# MCU.net
KiCad netlist of a schematic drawn in Altium Designer
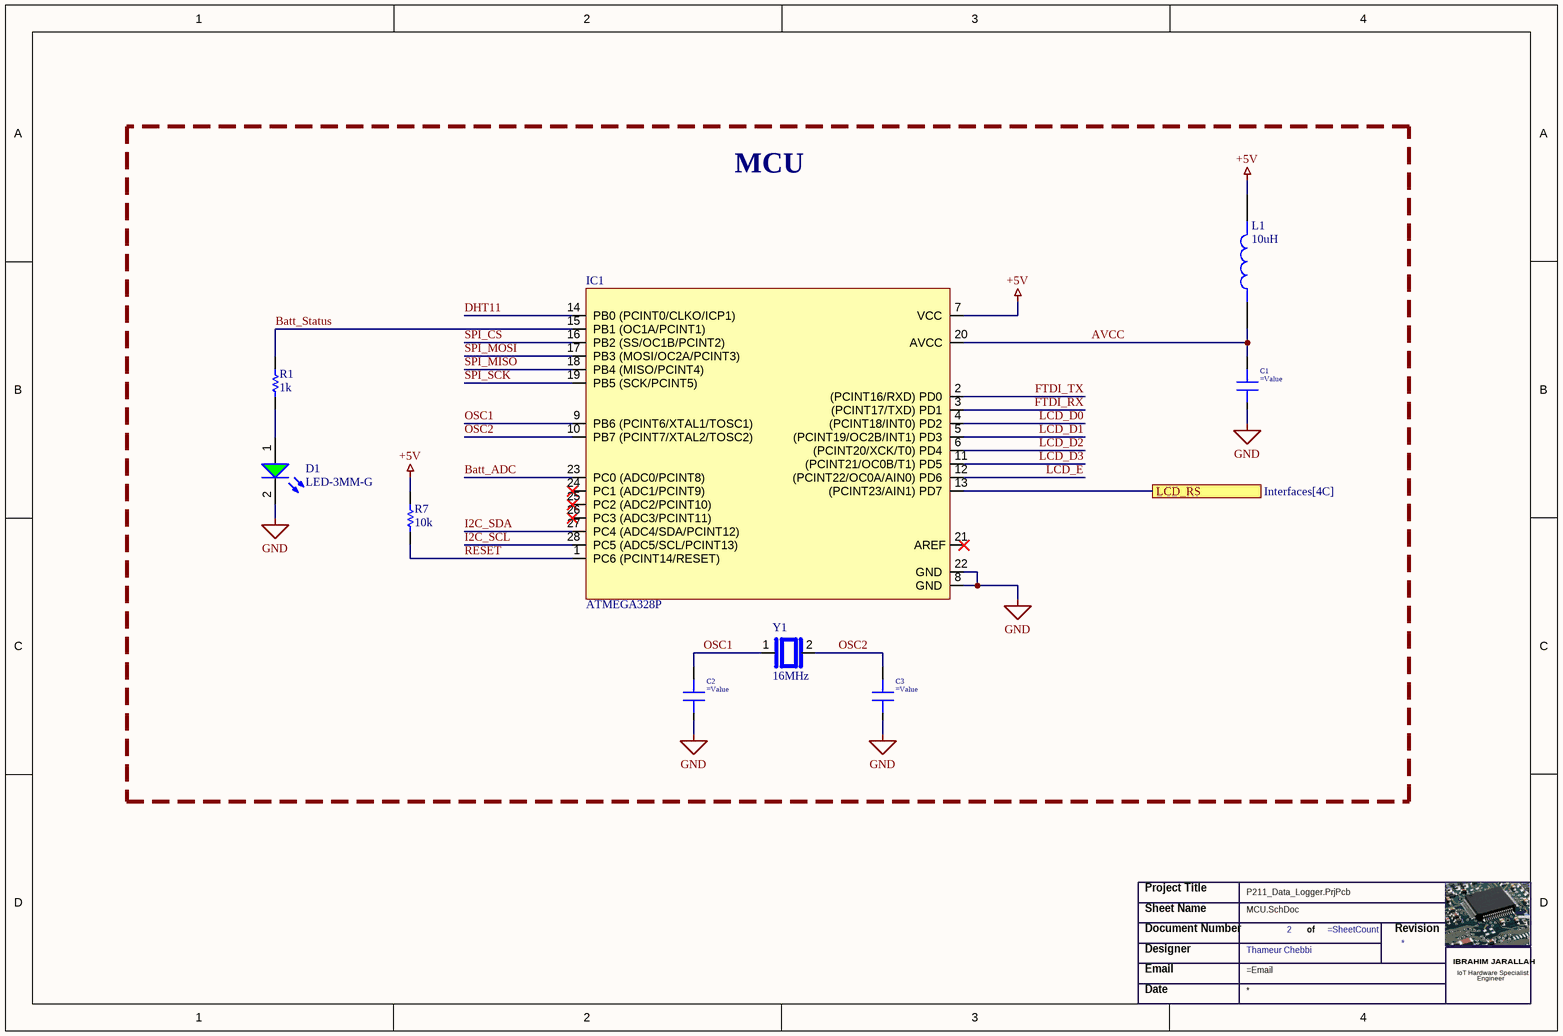
[diagram p0: MCU.SchDoc]

(export (version "E")
  (design (tool "Eeschema 10.0.6"))
  (components
    (comp (ref "C1")
      (value "~")
      (footprint "C 0805(2012)x0.85")
      (description "SMD 0805     50V X7R 10%")
      (fields (field (name "MANUFACTURER") "Samsung") (field (name "PUBLISHER") "Hefest"))
      (libsource (lib "SCH_THA") (part "C 0805    50V X7R - 0*"))
    )
    (comp (ref "C2")
      (value "~")
      (footprint "C 0805(2012)x0.85")
      (description "SMD 0805     50V X7R 10%")
      (fields (field (name "MANUFACTURER") "Samsung") (field (name "PUBLISHER") "Hefest"))
      (libsource (lib "SCH_THA") (part "C 0805    50V X7R - 0*"))
    )
    (comp (ref "C3")
      (value "~")
      (footprint "C 0805(2012)x0.85")
      (description "SMD 0805     50V X7R 10%")
      (fields (field (name "MANUFACTURER") "Samsung") (field (name "PUBLISHER") "Hefest"))
      (libsource (lib "SCH_THA") (part "C 0805    50V X7R - 0*"))
    )
    (comp (ref "D1")
      (value "LED-3MM-G")
      (footprint "LED-2.54MM-G")
      (libsource (lib "SCH_THA") (part "LED-3MM-G"))
    )
    (comp (ref "IC1")
      (value "ATMEGA328P")
      (footprint "DIP28_P2.54mm_7.62mm")
      (description "Microcontroller, ATmega328P, 8-bit, PDIP-28 32kB Flash")
      (libsource (lib "Symbol_Lib") (part "IC_ATMEGA328P_PDIP"))
    )
    (comp (ref "L1")
      (value "10uH")
      (footprint "IND_LQH31MN100J03L")
      (description "Wire Wound Ferrite Inductor for General Circuits")
      (fields (field (name "MF") "{'manufacturer': u'Murata'}") (field (name "MP") "LQH31MN100J03L"))
      (libsource (lib "SCH_THA") (part "LQH31MN100J03L"))
    )
    (comp (ref "R1")
      (value "1k")
      (footprint "RESC2013X50X30LL20T20")
      (libsource (lib "SCH_THA") (part "RES-0805-SMD"))
    )
    (comp (ref "R7")
      (value "10k")
      (footprint "RESC2013X50X30LL20T20")
      (libsource (lib "SCH_THA") (part "RES-0805-SMD"))
    )
    (comp (ref "Y1")
      (value "16MHz")
      (footprint "XTAL_HC49P488W43L1150T466H350")
      (description "HC49US Series 16 MHz Â±30 ppm 18 pF -20 to +70 Â°C Through Hole AT-CUT Crystal")
      (fields
        (field (name "MF") "{'manufacturer': u'Citizen Finedevice'}")
        (field (name "MP") "HC-49/U-S16000000ABJB")
      )
      (libsource (lib "SCH_THA") (part "HC-49/U-S16000000ABJB"))
    )
  )
  (nets
    (net (code "1") (name "+5V") (class "Default")
      (node (ref "IC1") (pin "7") (pinfunction "VCC_7") (pintype "power_in"))
      (node (ref "L1") (pin "2") (pinfunction "2_2") (pintype "passive"))
      (node (ref "R7") (pin "1") (pinfunction "1_1") (pintype "passive"))
    )
    (net (code "2") (name "/AVCC") (class "Default")
      (node (ref "C1") (pin "2") (pinfunction "2_2") (pintype "passive"))
      (node (ref "IC1") (pin "20") (pinfunction "AVCC_20") (pintype "power_in"))
      (node (ref "L1") (pin "1") (pinfunction "1_1") (pintype "passive"))
    )
    (net (code "3") (name "/Batt_ADC") (class "Default")
      (node (ref "IC1") (pin "23") (pinfunction "PC0_(ADC0/PCINT8)_23") (pintype "passive"))
    )
    (net (code "4") (name "/Batt_Status") (class "Default")
      (node (ref "IC1") (pin "15") (pinfunction "PB1_(OC1A/PCINT1)_15") (pintype "passive"))
      (node (ref "R1") (pin "1") (pinfunction "1_1") (pintype "passive"))
    )
    (net (code "5") (name "/DHT11") (class "Default")
      (node (ref "IC1") (pin "14") (pinfunction "PB0_(PCINT0/CLKO/ICP1)_14") (pintype "passive"))
    )
    (net (code "6") (name "/FTDI_RX") (class "Default")
      (node (ref "IC1") (pin "3") (pinfunction "(PCINT17/TXD)_PD1_3") (pintype "passive"))
    )
    (net (code "7") (name "/FTDI_TX") (class "Default")
      (node (ref "IC1") (pin "2") (pinfunction "(PCINT16/RXD)_PD0_2") (pintype "passive"))
    )
    (net (code "8") (name "/I2C_SCL") (class "Default")
      (node (ref "IC1") (pin "28") (pinfunction "PC5_(ADC5/SCL/PCINT13)_28") (pintype "passive"))
    )
    (net (code "9") (name "/I2C_SDA") (class "Default")
      (node (ref "IC1") (pin "27") (pinfunction "PC4_(ADC4/SDA/PCINT12)_27") (pintype "passive"))
    )
    (net (code "10") (name "/LCD_D0") (class "Default")
      (node (ref "IC1") (pin "4") (pinfunction "(PCINT18/INT0)_PD2_4") (pintype "passive"))
    )
    (net (code "11") (name "/LCD_D1") (class "Default")
      (node (ref "IC1") (pin "5") (pinfunction "(PCINT19/OC2B/INT1)_PD3_5") (pintype "passive"))
    )
    (net (code "12") (name "/LCD_D2") (class "Default")
      (node (ref "IC1") (pin "6") (pinfunction "(PCINT20/XCK/T0)_PD4_6") (pintype "passive"))
    )
    (net (code "13") (name "/LCD_D3") (class "Default")
      (node (ref "IC1") (pin "11") (pinfunction "(PCINT21/OC0B/T1)_PD5_11") (pintype "passive"))
    )
    (net (code "14") (name "/LCD_E") (class "Default")
      (node (ref "IC1") (pin "12") (pinfunction "(PCINT22/OC0A/AIN0)_PD6_12") (pintype "passive"))
    )
    (net (code "15") (name "/LCD_RS") (class "Default")
      (node (ref "IC1") (pin "13") (pinfunction "(PCINT23/AIN1)_PD7_13") (pintype "passive"))
    )
    (net (code "16") (name "/OSC1") (class "Default")
      (node (ref "C2") (pin "2") (pinfunction "2_2") (pintype "passive"))
      (node (ref "IC1") (pin "9") (pinfunction "PB6_(PCINT6/XTAL1/TOSC1)_9") (pintype "passive"))
      (node (ref "Y1") (pin "1") (pinfunction "1_1") (pintype "passive"))
    )
    (net (code "17") (name "/OSC2") (class "Default")
      (node (ref "C3") (pin "2") (pinfunction "2_2") (pintype "passive"))
      (node (ref "IC1") (pin "10") (pinfunction "PB7_(PCINT7/XTAL2/TOSC2)_10") (pintype "passive"))
      (node (ref "Y1") (pin "2") (pinfunction "2_2") (pintype "passive"))
    )
    (net (code "18") (name "/RESET") (class "Default")
      (node (ref "IC1") (pin "1") (pinfunction "PC6_(PCINT14/RESET)_1") (pintype "passive"))
      (node (ref "R7") (pin "2") (pinfunction "2_2") (pintype "passive"))
    )
    (net (code "19") (name "/SPI_CS") (class "Default")
      (node (ref "IC1") (pin "16") (pinfunction "PB2_(SS/OC1B/PCINT2)_16") (pintype "passive"))
    )
    (net (code "20") (name "/SPI_MISO") (class "Default")
      (node (ref "IC1") (pin "18") (pinfunction "PB4_(MISO/PCINT4)_18") (pintype "passive"))
    )
    (net (code "21") (name "/SPI_MOSI") (class "Default")
      (node (ref "IC1") (pin "17") (pinfunction "PB3_(MOSI/OC2A/PCINT3)_17") (pintype "passive"))
    )
    (net (code "22") (name "/SPI_SCK") (class "Default")
      (node (ref "IC1") (pin "19") (pinfunction "PB5_(SCK/PCINT5)_19") (pintype "passive"))
    )
    (net (code "23") (name "GND") (class "Default")
      (node (ref "C1") (pin "1") (pinfunction "1_1") (pintype "passive"))
      (node (ref "C2") (pin "1") (pinfunction "1_1") (pintype "passive"))
      (node (ref "C3") (pin "1") (pinfunction "1_1") (pintype "passive"))
      (node (ref "D1") (pin "2") (pinfunction "K_2") (pintype "passive"))
      (node (ref "IC1") (pin "22") (pinfunction "GND_22") (pintype "power_in"))
      (node (ref "IC1") (pin "8") (pinfunction "GND_8") (pintype "power_in"))
    )
    (net (code "24") (name "Net-(D1-A)") (class "Default")
      (node (ref "D1") (pin "1") (pinfunction "A_1") (pintype "passive"))
      (node (ref "R1") (pin "2") (pinfunction "2_2") (pintype "passive"))
    )
    (net (code "25") (name "unconnected-(IC1-AREF-Pad21)") (class "Default")
      (node (ref "IC1") (pin "21") (pinfunction "AREF_21") (pintype "power_in+no_connect"))
    )
    (net (code "26") (name "unconnected-(IC1-PC1_(ADC1{slash}PCINT9)-Pad24)") (class "Default")
      (node (ref "IC1") (pin "24") (pinfunction "PC1_(ADC1/PCINT9)_24") (pintype "passive+no_connect"))
    )
    (net (code "27") (name "unconnected-(IC1-PC2_(ADC2{slash}PCINT10)-Pad25)") (class "Default")
      (node (ref "IC1") (pin "25") (pinfunction "PC2_(ADC2/PCINT10)_25") (pintype "passive+no_connect"))
    )
    (net (code "28") (name "unconnected-(IC1-PC3_(ADC3{slash}PCINT11)-Pad26)") (class "Default")
      (node (ref "IC1") (pin "26") (pinfunction "PC3_(ADC3/PCINT11)_26") (pintype "passive+no_connect"))
    )
  )
)
